# mini_water_station_2020-11-22_21-22-46.net
KiCad netlist of a schematic drawn in EasyEDA
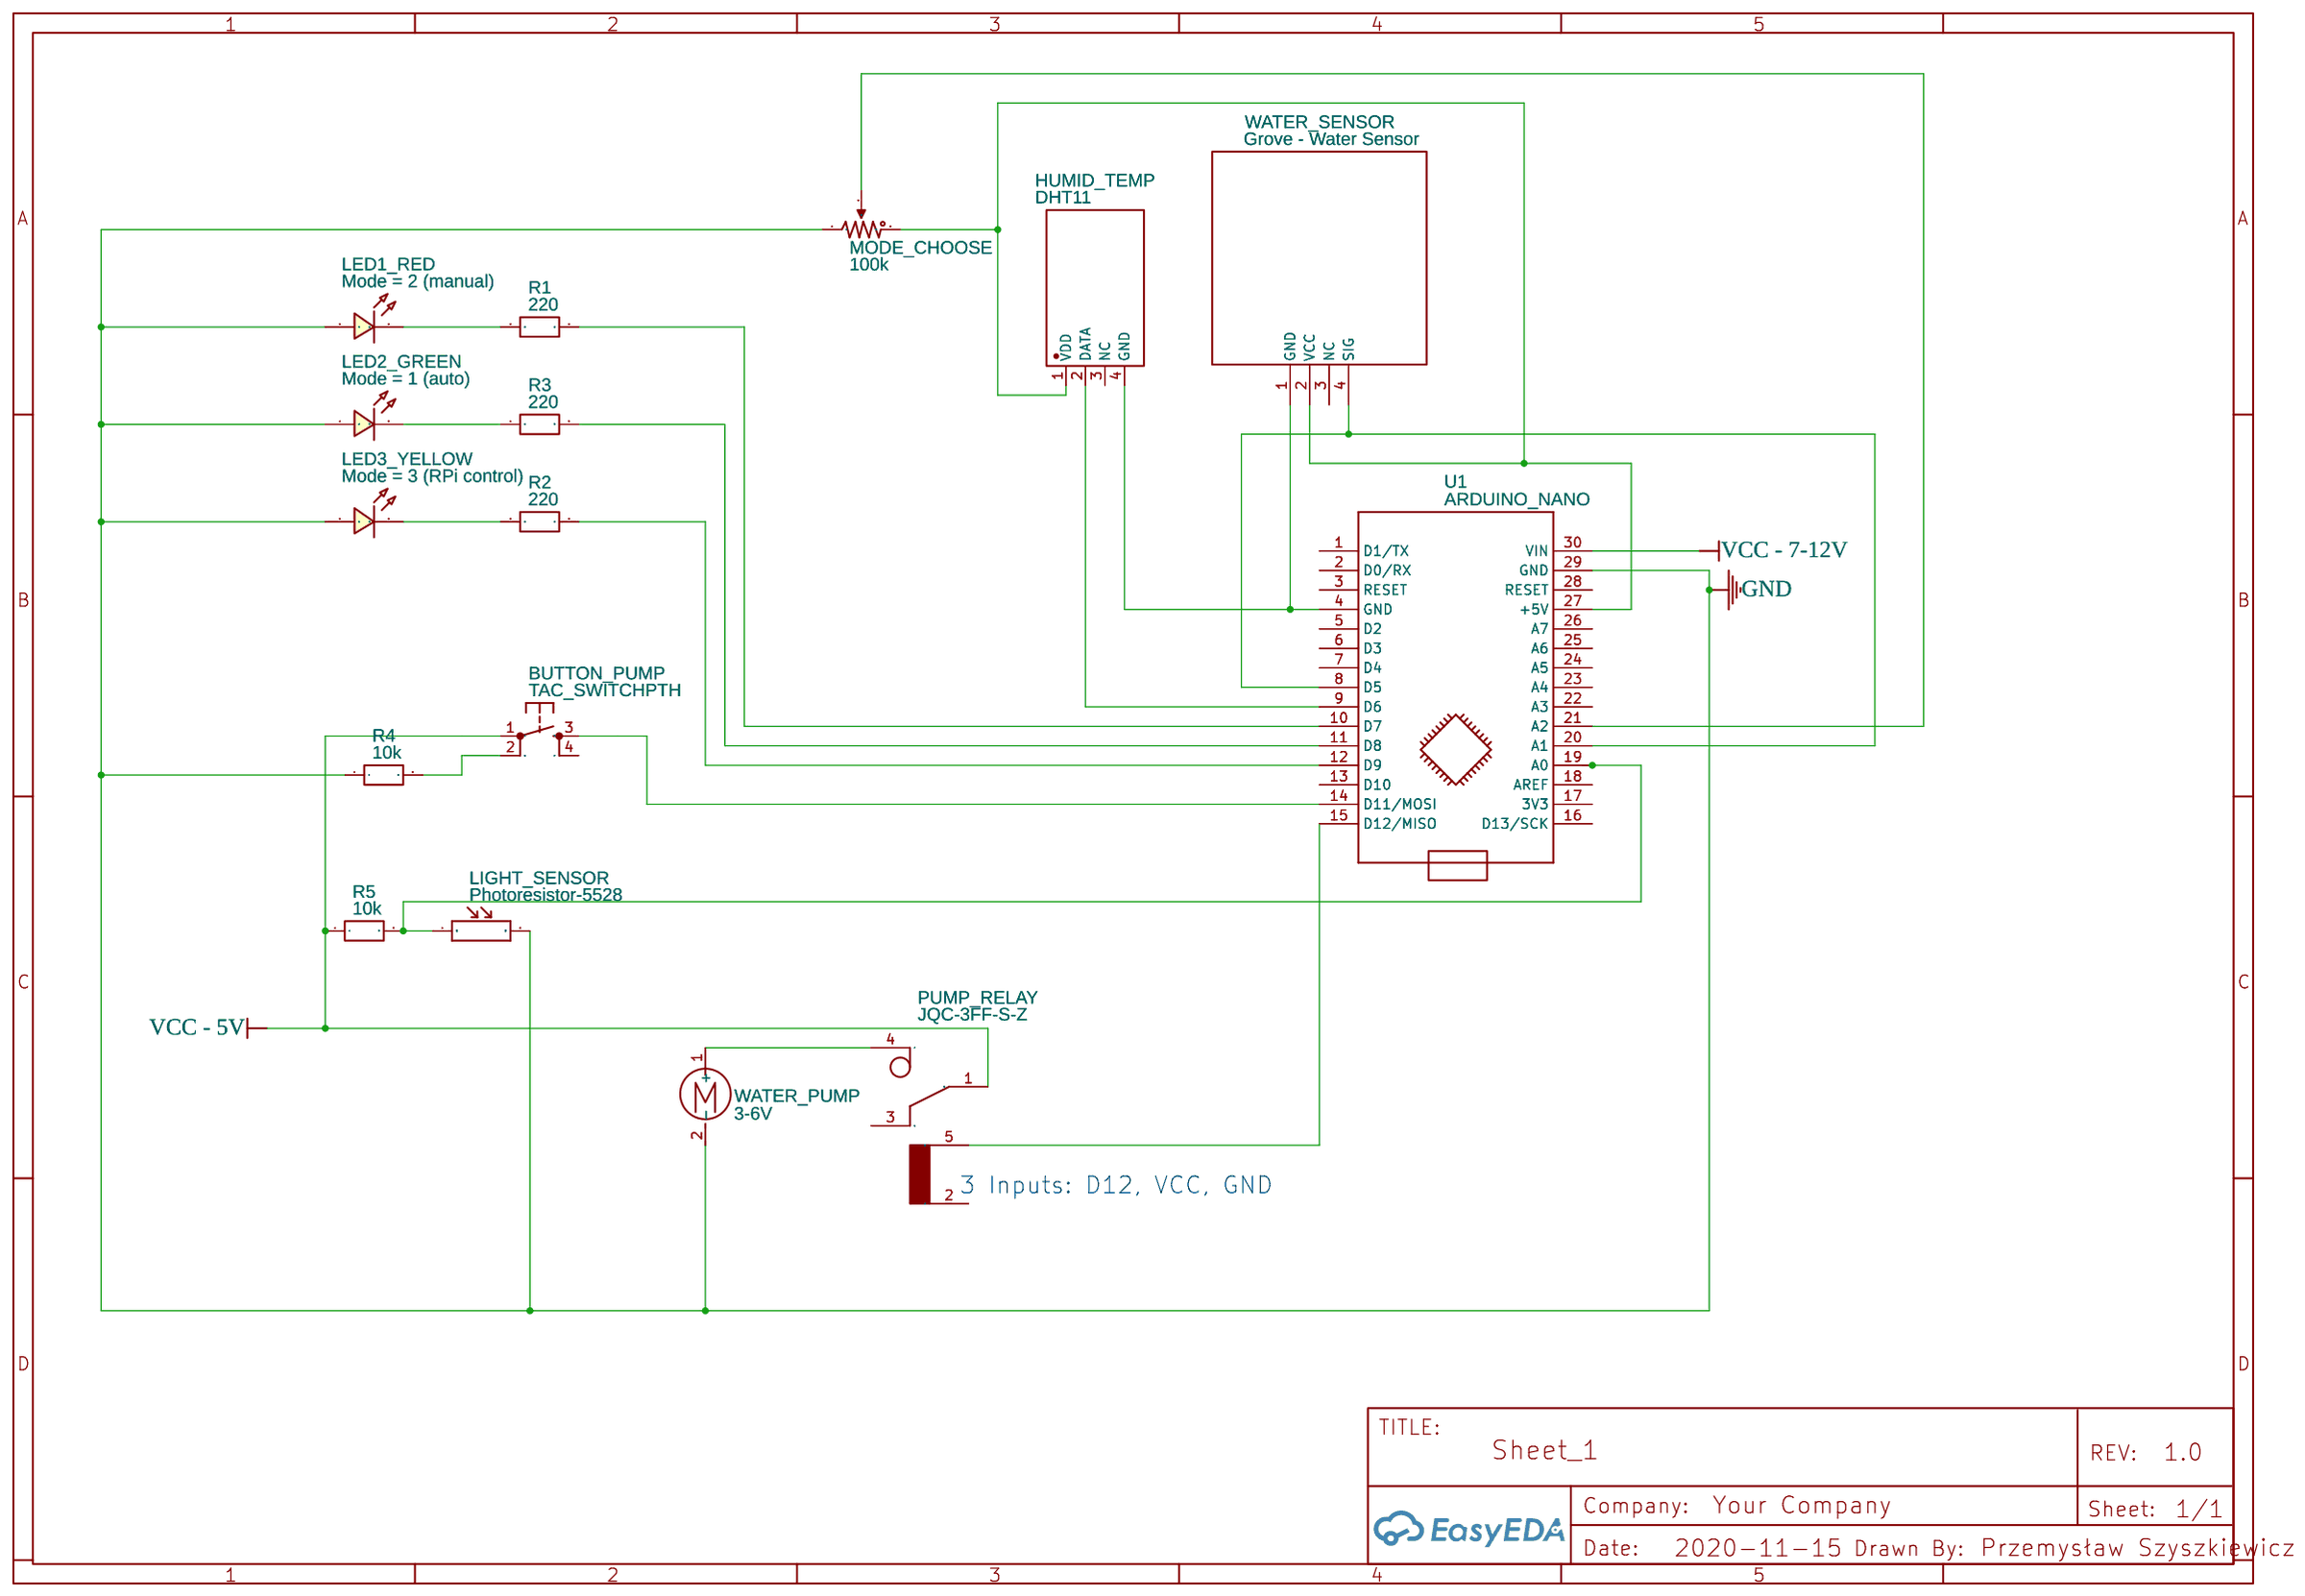
[diagram p0: schematic sheet]

(export (version "E")
  (design (tool "Eeschema 10.0.6"))
  (components
    (comp (ref "BUTTON_PUMP") (value "TAC_SWITCHPTH") (libsource (lib "") (part "TAC_SWITCHPTH")))
    (comp (ref "HUMID_TEMP")
      (value "DHT11")
      (fields (field (name "BOM_Supplier Part") "C117051"))
      (libsource (lib "") (part "DHT11"))
    )
    (comp (ref "LED1_RED")
      (value "Mode = 2 (manual)")
      (fields
        (field (name "BOM_Manufacturer Part") "19-217/R6C-AL1M2VY/3T")
        (field (name "BOM_Supplier Part") "C72044")
      )
      (libsource (lib "") (part "LED-0603_R"))
    )
    (comp (ref "LED2_GREEN")
      (value "Mode = 1 (auto)")
      (fields
        (field (name "BOM_Manufacturer Part") "19-217/GHC-YR1S2/3T")
        (field (name "BOM_Supplier Part") "C72043")
      )
      (libsource (lib "") (part "LED-0603_G"))
    )
    (comp (ref "LED3_YELLOW")
      (value "Mode = 3 (RPi control)")
      (fields
        (field (name "BOM_Manufacturer Part") "19-217/BHC-ZL1M2RY/3T")
        (field (name "BOM_Supplier Part") "C72041")
      )
      (libsource (lib "") (part "LED-0603_B"))
    )
    (comp (ref "LIGHT_SENSOR") (value "Photoresistor-5528") (libsource (lib "") (part "Photoresistor-5528")))
    (comp (ref "MODE_CHOOSE") (value "100k") (libsource (lib "") (part "Potentiometer")))
    (comp (ref "PUMP_RELAY") (value "JQC-3FF-S-Z") (libsource (lib "") (part "JQC-3FF-S-Z")))
    (comp (ref "R1") (value "220") (libsource (lib "") (part "R_0603_EU")))
    (comp (ref "R2") (value "220") (libsource (lib "") (part "R_0603_EU")))
    (comp (ref "R3") (value "220") (libsource (lib "") (part "R_0603_EU")))
    (comp (ref "R4") (value "10k") (libsource (lib "") (part "R_0603_EU")))
    (comp (ref "R5") (value "10k") (libsource (lib "") (part "R_0603_EU")))
    (comp (ref "U1") (value "ARDUINO_NANO") (libsource (lib "") (part "ARDUINO_NANO")))
    (comp (ref "WATER_PUMP") (value "3-6V") (libsource (lib "") (part "Motor_DC")))
    (comp (ref "WATER_SENSOR")
      (value "Grove - Water Sensor")
      (fields (field (name "BOM_Supplier Part") "undefined"))
      (libsource (lib "") (part "Grove - Water Sensor"))
    )
  )
  (nets
    (net (code "1") (name "GND") (class "Default")
      (node (ref "LED1_RED") (pin "1") (pinfunction "1_1") (pintype "unspecified"))
      (node (ref "LED2_GREEN") (pin "1") (pinfunction "1_1") (pintype "unspecified"))
      (node (ref "LED3_YELLOW") (pin "1") (pinfunction "1_1") (pintype "unspecified"))
      (node (ref "LIGHT_SENSOR") (pin "2") (pinfunction "P$2_2") (pintype "unspecified"))
      (node (ref "MODE_CHOOSE") (pin "1") (pinfunction "1_1") (pintype "unspecified"))
      (node (ref "R4") (pin "1") (pinfunction "1_1") (pintype "unspecified"))
      (node (ref "U1") (pin "29") (pinfunction "GND_29") (pintype "unspecified"))
      (node (ref "WATER_PUMP") (pin "2") (pinfunction "-_2") (pintype "unspecified"))
    )
    (net (code "2") (name "Net-(BUTTON_PUMP-Pad2)") (class "Default")
      (node (ref "BUTTON_PUMP") (pin "2") (pinfunction "2_2") (pintype "unspecified"))
      (node (ref "R4") (pin "2") (pinfunction "2_2") (pintype "unspecified"))
    )
    (net (code "3") (name "Net-(HUMID_TEMP-DATA)") (class "Default")
      (node (ref "HUMID_TEMP") (pin "2") (pinfunction "DATA_2") (pintype "unspecified"))
      (node (ref "U1") (pin "9") (pinfunction "D6_9") (pintype "unspecified"))
    )
    (net (code "4") (name "Net-(HUMID_TEMP-GND)") (class "Default")
      (node (ref "HUMID_TEMP") (pin "4") (pinfunction "GND_4") (pintype "unspecified"))
      (node (ref "U1") (pin "4") (pinfunction "GND_4") (pintype "unspecified"))
      (node (ref "WATER_SENSOR") (pin "1") (pinfunction "GND_1") (pintype "unspecified"))
    )
    (net (code "5") (name "Net-(HUMID_TEMP-VDD)") (class "Default")
      (node (ref "HUMID_TEMP") (pin "1") (pinfunction "VDD_1") (pintype "unspecified"))
      (node (ref "MODE_CHOOSE") (pin "3") (pinfunction "2_3") (pintype "unspecified"))
      (node (ref "U1") (pin "27") (pinfunction "+5V_27") (pintype "unspecified"))
      (node (ref "WATER_SENSOR") (pin "2") (pinfunction "VCC_2") (pintype "unspecified"))
    )
    (net (code "6") (name "Net-(LED1_RED-Pad2)") (class "Default")
      (node (ref "LED1_RED") (pin "2") (pinfunction "2_2") (pintype "unspecified"))
      (node (ref "R1") (pin "1") (pinfunction "1_1") (pintype "unspecified"))
    )
    (net (code "7") (name "Net-(LED2_GREEN-Pad2)") (class "Default")
      (node (ref "LED2_GREEN") (pin "2") (pinfunction "2_2") (pintype "unspecified"))
      (node (ref "R3") (pin "1") (pinfunction "1_1") (pintype "unspecified"))
    )
    (net (code "8") (name "Net-(LED3_YELLOW-Pad2)") (class "Default")
      (node (ref "LED3_YELLOW") (pin "2") (pinfunction "2_2") (pintype "unspecified"))
      (node (ref "R2") (pin "1") (pinfunction "1_1") (pintype "unspecified"))
    )
    (net (code "9") (name "Net-(LIGHT_SENSOR-P$1)") (class "Default")
      (node (ref "LIGHT_SENSOR") (pin "1") (pinfunction "P$1_1") (pintype "unspecified"))
      (node (ref "R5") (pin "2") (pinfunction "2_2") (pintype "unspecified"))
      (node (ref "U1") (pin "19") (pinfunction "A0_19") (pintype "unspecified"))
    )
    (net (code "10") (name "Net-(MODE_CHOOSE-3)") (class "Default")
      (node (ref "MODE_CHOOSE") (pin "2") (pinfunction "3_2") (pintype "unspecified"))
      (node (ref "U1") (pin "21") (pinfunction "A2_21") (pintype "unspecified"))
    )
    (net (code "11") (name "Net-(U1-A1)") (class "Default")
      (node (ref "U1") (pin "20") (pinfunction "A1_20") (pintype "unspecified"))
      (node (ref "U1") (pin "8") (pinfunction "D5_8") (pintype "unspecified"))
      (node (ref "WATER_SENSOR") (pin "4") (pinfunction "SIG_4") (pintype "unspecified"))
    )
    (net (code "12") (name "Net-(U1-D7)") (class "Default")
      (node (ref "R1") (pin "2") (pinfunction "2_2") (pintype "unspecified"))
      (node (ref "U1") (pin "10") (pinfunction "D7_10") (pintype "unspecified"))
    )
    (net (code "13") (name "Net-(U1-D8)") (class "Default")
      (node (ref "R3") (pin "2") (pinfunction "2_2") (pintype "unspecified"))
      (node (ref "U1") (pin "11") (pinfunction "D8_11") (pintype "unspecified"))
    )
    (net (code "14") (name "Net-(U1-D9)") (class "Default")
      (node (ref "R2") (pin "2") (pinfunction "2_2") (pintype "unspecified"))
      (node (ref "U1") (pin "12") (pinfunction "D9_12") (pintype "unspecified"))
    )
    (net (code "15") (name "Net-(U1-D11{slash}MOSI)") (class "Default")
      (node (ref "BUTTON_PUMP") (pin "3") (pinfunction "3_3") (pintype "unspecified"))
      (node (ref "U1") (pin "14") (pinfunction "D11/MOSI_14") (pintype "unspecified"))
    )
    (net (code "16") (name "Net-(U1-D12{slash}MISO)") (class "Default")
      (node (ref "PUMP_RELAY") (pin "5") (pinfunction "5_5") (pintype "unspecified"))
      (node (ref "U1") (pin "15") (pinfunction "D12/MISO_15") (pintype "unspecified"))
    )
    (net (code "17") (name "Net-(WATER_PUMP-+)") (class "Default")
      (node (ref "PUMP_RELAY") (pin "4") (pinfunction "4_4") (pintype "unspecified"))
      (node (ref "WATER_PUMP") (pin "1") (pinfunction "+_1") (pintype "unspecified"))
    )
    (net (code "18") (name "VCC - 5V") (class "Default")
      (node (ref "BUTTON_PUMP") (pin "1") (pinfunction "1_1") (pintype "unspecified"))
      (node (ref "PUMP_RELAY") (pin "1") (pinfunction "1_1") (pintype "unspecified"))
      (node (ref "R5") (pin "1") (pinfunction "1_1") (pintype "unspecified"))
    )
    (net (code "19") (name "VCC - 7-12V") (class "Default")
      (node (ref "U1") (pin "30") (pinfunction "VIN_30") (pintype "unspecified"))
    )
    (net (code "20") (name "unconnected-(BUTTON_PUMP-Pad4)") (class "Default")
      (node (ref "BUTTON_PUMP") (pin "4") (pinfunction "4_4") (pintype "unspecified"))
    )
    (net (code "21") (name "unconnected-(HUMID_TEMP-NC-Pad3)") (class "Default")
      (node (ref "HUMID_TEMP") (pin "3") (pinfunction "NC_3") (pintype "unspecified"))
    )
    (net (code "22") (name "unconnected-(PUMP_RELAY-Pad2)") (class "Default")
      (node (ref "PUMP_RELAY") (pin "2") (pinfunction "2_2") (pintype "unspecified"))
    )
    (net (code "23") (name "unconnected-(PUMP_RELAY-Pad3)") (class "Default")
      (node (ref "PUMP_RELAY") (pin "3") (pinfunction "3_3") (pintype "unspecified"))
    )
    (net (code "24") (name "unconnected-(U1-3V3-Pad17)") (class "Default")
      (node (ref "U1") (pin "17") (pinfunction "3V3_17") (pintype "unspecified"))
    )
    (net (code "25") (name "unconnected-(U1-A3-Pad22)") (class "Default")
      (node (ref "U1") (pin "22") (pinfunction "A3_22") (pintype "unspecified"))
    )
    (net (code "26") (name "unconnected-(U1-A4-Pad23)") (class "Default")
      (node (ref "U1") (pin "23") (pinfunction "A4_23") (pintype "unspecified"))
    )
    (net (code "27") (name "unconnected-(U1-A5-Pad24)") (class "Default")
      (node (ref "U1") (pin "24") (pinfunction "A5_24") (pintype "unspecified"))
    )
    (net (code "28") (name "unconnected-(U1-A6-Pad25)") (class "Default")
      (node (ref "U1") (pin "25") (pinfunction "A6_25") (pintype "unspecified"))
    )
    (net (code "29") (name "unconnected-(U1-A7-Pad26)") (class "Default")
      (node (ref "U1") (pin "26") (pinfunction "A7_26") (pintype "unspecified"))
    )
    (net (code "30") (name "unconnected-(U1-AREF-Pad18)") (class "Default")
      (node (ref "U1") (pin "18") (pinfunction "AREF_18") (pintype "unspecified"))
    )
    (net (code "31") (name "unconnected-(U1-D0{slash}RX-Pad2)") (class "Default")
      (node (ref "U1") (pin "2") (pinfunction "D0/RX_2") (pintype "unspecified"))
    )
    (net (code "32") (name "unconnected-(U1-D1{slash}TX-Pad1)") (class "Default")
      (node (ref "U1") (pin "1") (pinfunction "D1/TX_1") (pintype "unspecified"))
    )
    (net (code "33") (name "unconnected-(U1-D2-Pad5)") (class "Default")
      (node (ref "U1") (pin "5") (pinfunction "D2_5") (pintype "unspecified"))
    )
    (net (code "34") (name "unconnected-(U1-D3-Pad6)") (class "Default")
      (node (ref "U1") (pin "6") (pinfunction "D3_6") (pintype "unspecified"))
    )
    (net (code "35") (name "unconnected-(U1-D4-Pad7)") (class "Default")
      (node (ref "U1") (pin "7") (pinfunction "D4_7") (pintype "unspecified"))
    )
    (net (code "36") (name "unconnected-(U1-D10-Pad13)") (class "Default")
      (node (ref "U1") (pin "13") (pinfunction "D10_13") (pintype "unspecified"))
    )
    (net (code "37") (name "unconnected-(U1-D13{slash}SCK-Pad16)") (class "Default")
      (node (ref "U1") (pin "16") (pinfunction "D13/SCK_16") (pintype "unspecified"))
    )
    (net (code "38") (name "unconnected-(U1-RESET-Pad3)") (class "Default")
      (node (ref "U1") (pin "3") (pinfunction "RESET_3") (pintype "unspecified"))
    )
    (net (code "39") (name "unconnected-(U1-RESET-Pad28)") (class "Default")
      (node (ref "U1") (pin "28") (pinfunction "RESET_28") (pintype "unspecified"))
    )
    (net (code "40") (name "unconnected-(WATER_SENSOR-NC-Pad3)") (class "Default")
      (node (ref "WATER_SENSOR") (pin "3") (pinfunction "NC_3") (pintype "unspecified"))
    )
  )
)
